# Actuators.net
KiCad netlist of a schematic drawn in Altium Designer
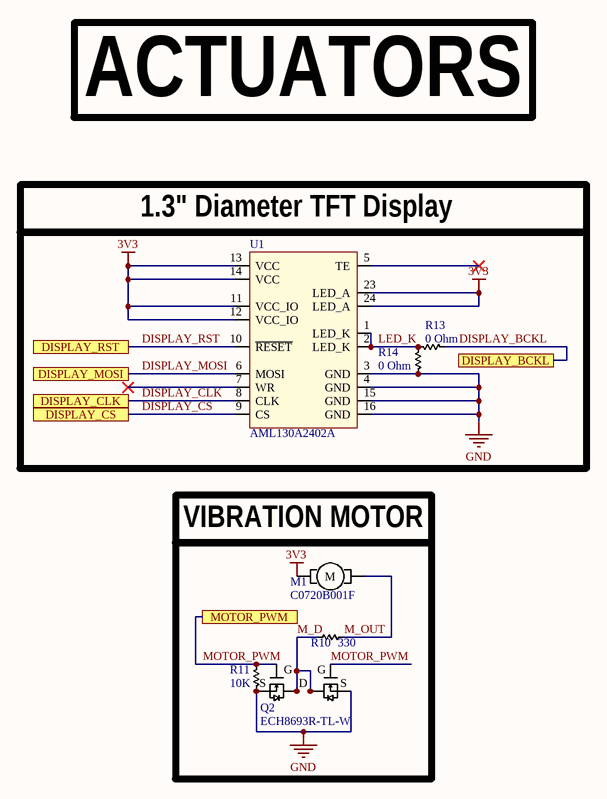
[diagram p0: Actuators.SchDoc]

(export (version "E")
  (design (tool "Eeschema 10.0.6"))
  (components
    (comp (ref "M1")
      (value "C0720B001F")
      (footprint "C0720B001F")
      (description "DC Motor Vibration, ERM 10000 RPM 3VDC")
      (libsource (lib "smLib") (part "C0720B001F"))
    )
    (comp (ref "Q2")
      (value "ECH8693R-TL-W")
      (footprint "ECH8693R-TL-W")
      (description "Mosfet Array 2 N-Channel (Dual) Common Drain 24V 14A 1.4W Surface Mount SOT-28FL/ECH8")
      (libsource (lib "smLib") (part "ECH8693R-TL-W"))
    )
    (comp (ref "R10")
      (value "330")
      (footprint "RES_0603_HIGH")
      (description "0603 Resistor")
      (libsource (lib "smLib") (part "Resistor_0603"))
    )
    (comp (ref "R11")
      (value "10K")
      (footprint "RES_0603_HIGH")
      (description "0603 Resistor")
      (libsource (lib "smLib") (part "Resistor_0603"))
    )
    (comp (ref "R13")
      (value "0 Ohm")
      (footprint "RES_0603_HIGH")
      (description "0603 Resistor")
      (libsource (lib "smLib") (part "Resistor_0603"))
    )
    (comp (ref "R14")
      (value "0 Ohm")
      (footprint "RES_0603_HIGH")
      (description "0603 Resistor")
      (libsource (lib "smLib") (part "Resistor_0603"))
    )
    (comp (ref "U1")
      (value "AML130A2402A")
      (footprint "AML130A2402A")
      (description "AML130A2402A Round 1.3\" TFT Display")
      (libsource (lib "smLib") (part "AML130A2402A"))
    )
  )
  (nets
    (net (code "1") (name "/DISPLAY_BCKL") (class "Default")
      (node (ref "R13") (pin "1") (pinfunction "1_1") (pintype "passive"))
    )
    (net (code "2") (name "/DISPLAY_CLK") (class "Default")
      (node (ref "U1") (pin "8") (pinfunction "CLK_8") (pintype "passive"))
    )
    (net (code "3") (name "/DISPLAY_CS") (class "Default")
      (node (ref "U1") (pin "9") (pinfunction "CS_9") (pintype "passive"))
    )
    (net (code "4") (name "/DISPLAY_MOSI") (class "Default")
      (node (ref "U1") (pin "6") (pinfunction "MOSI_6") (pintype "passive"))
    )
    (net (code "5") (name "/DISPLAY_RST") (class "Default")
      (node (ref "U1") (pin "10") (pinfunction "~{RESET}_10") (pintype "passive"))
    )
    (net (code "6") (name "/LED_K") (class "Default")
      (node (ref "R13") (pin "2") (pinfunction "2_2") (pintype "passive"))
      (node (ref "R14") (pin "1") (pinfunction "1_1") (pintype "passive"))
      (node (ref "U1") (pin "1") (pinfunction "LED_K_1") (pintype "passive"))
      (node (ref "U1") (pin "2") (pinfunction "LED_K_2") (pintype "passive"))
    )
    (net (code "7") (name "/MOTOR_PWM") (class "Default")
      (node (ref "Q2") (pin "2") (pinfunction "G1_2") (pintype "passive"))
      (node (ref "Q2") (pin "4") (pinfunction "G2_4") (pintype "passive"))
      (node (ref "R11") (pin "2") (pinfunction "2_2") (pintype "passive"))
    )
    (net (code "8") (name "/M_D") (class "Default")
      (node (ref "Q2") (pin "5") (pinfunction "D_5") (pintype "passive"))
      (node (ref "Q2") (pin "6") (pinfunction "D_6") (pintype "passive"))
      (node (ref "Q2") (pin "7") (pinfunction "D_7") (pintype "passive"))
      (node (ref "Q2") (pin "8") (pinfunction "D_8") (pintype "passive"))
      (node (ref "R10") (pin "1") (pinfunction "1_1") (pintype "passive"))
    )
    (net (code "9") (name "/M_OUT") (class "Default")
      (node (ref "M1") (pin "2") (pinfunction "2_2") (pintype "passive"))
      (node (ref "R10") (pin "2") (pinfunction "2_2") (pintype "passive"))
    )
    (net (code "10") (name "3V3") (class "Default")
      (node (ref "M1") (pin "1") (pinfunction "1_1") (pintype "passive"))
      (node (ref "U1") (pin "11") (pinfunction "VCC_IO_11") (pintype "passive"))
      (node (ref "U1") (pin "12") (pinfunction "VCC_IO_12") (pintype "passive"))
      (node (ref "U1") (pin "13") (pinfunction "VCC_13") (pintype "passive"))
      (node (ref "U1") (pin "14") (pinfunction "VCC_14") (pintype "passive"))
      (node (ref "U1") (pin "23") (pinfunction "LED_A_23") (pintype "passive"))
      (node (ref "U1") (pin "24") (pinfunction "LED_A_24") (pintype "passive"))
    )
    (net (code "11") (name "GND") (class "Default")
      (node (ref "Q2") (pin "1") (pinfunction "S1_1") (pintype "passive"))
      (node (ref "Q2") (pin "3") (pinfunction "S2_3") (pintype "passive"))
      (node (ref "R11") (pin "1") (pinfunction "1_1") (pintype "passive"))
      (node (ref "R14") (pin "2") (pinfunction "2_2") (pintype "passive"))
      (node (ref "U1") (pin "15") (pinfunction "GND_15") (pintype "passive"))
      (node (ref "U1") (pin "16") (pinfunction "GND_16") (pintype "passive"))
      (node (ref "U1") (pin "3") (pinfunction "GND_3") (pintype "passive"))
      (node (ref "U1") (pin "4") (pinfunction "GND_4") (pintype "passive"))
    )
    (net (code "12") (name "unconnected-(U1-TE-Pad5)") (class "Default")
      (node (ref "U1") (pin "5") (pinfunction "TE_5") (pintype "passive+no_connect"))
    )
    (net (code "13") (name "unconnected-(U1-WR-Pad7)") (class "Default")
      (node (ref "U1") (pin "7") (pinfunction "WR_7") (pintype "passive+no_connect"))
    )
  )
)
